# CONNECTORS2.net
KiCad netlist of a schematic drawn in Altium Designer
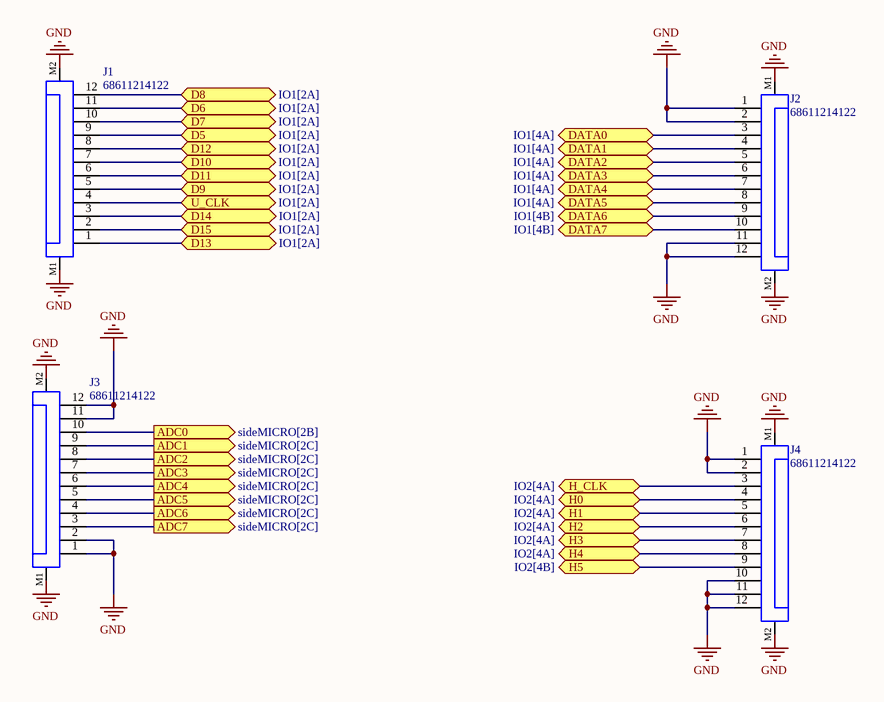
[diagram p0: CONNECTORS2.SchDoc]

(export (version "E")
  (design (tool "Eeschema 10.0.6"))
  (components
    (comp (ref "J1")
      (value "68611214122")
      (footprint "68611214122")
      (libsource (lib "Altium Content Vault") (part "FPC - 12P - 2MP"))
    )
    (comp (ref "J2")
      (value "68611214122")
      (footprint "68611214122")
      (libsource (lib "Altium Content Vault") (part "FPC - 12P - 2MP"))
    )
    (comp (ref "J3")
      (value "68611214122")
      (footprint "68611214122")
      (libsource (lib "Altium Content Vault") (part "FPC - 12P - 2MP"))
    )
    (comp (ref "J4")
      (value "68611214122")
      (footprint "68611214122")
      (libsource (lib "Altium Content Vault") (part "FPC - 12P - 2MP"))
    )
  )
  (nets
    (net (code "1") (name "/ADC0") (class "Default")
      (node (ref "J3") (pin "10") (pinfunction "10_10") (pintype "passive"))
    )
    (net (code "2") (name "/ADC1") (class "Default")
      (node (ref "J3") (pin "9") (pinfunction "9_9") (pintype "passive"))
    )
    (net (code "3") (name "/ADC2") (class "Default")
      (node (ref "J3") (pin "8") (pinfunction "8_8") (pintype "passive"))
    )
    (net (code "4") (name "/ADC3") (class "Default")
      (node (ref "J3") (pin "7") (pinfunction "7_7") (pintype "passive"))
    )
    (net (code "5") (name "/ADC4") (class "Default")
      (node (ref "J3") (pin "6") (pinfunction "6_6") (pintype "passive"))
    )
    (net (code "6") (name "/ADC5") (class "Default")
      (node (ref "J3") (pin "5") (pinfunction "5_5") (pintype "passive"))
    )
    (net (code "7") (name "/ADC6") (class "Default")
      (node (ref "J3") (pin "4") (pinfunction "4_4") (pintype "passive"))
    )
    (net (code "8") (name "/ADC7") (class "Default")
      (node (ref "J3") (pin "3") (pinfunction "3_3") (pintype "passive"))
    )
    (net (code "9") (name "/D5") (class "Default")
      (node (ref "J1") (pin "9") (pinfunction "9_9") (pintype "passive"))
    )
    (net (code "10") (name "/D6") (class "Default")
      (node (ref "J1") (pin "11") (pinfunction "11_11") (pintype "passive"))
    )
    (net (code "11") (name "/D7") (class "Default")
      (node (ref "J1") (pin "10") (pinfunction "10_10") (pintype "passive"))
    )
    (net (code "12") (name "/D8") (class "Default")
      (node (ref "J1") (pin "12") (pinfunction "12_12") (pintype "passive"))
    )
    (net (code "13") (name "/D9") (class "Default")
      (node (ref "J1") (pin "5") (pinfunction "5_5") (pintype "passive"))
    )
    (net (code "14") (name "/D10") (class "Default")
      (node (ref "J1") (pin "7") (pinfunction "7_7") (pintype "passive"))
    )
    (net (code "15") (name "/D11") (class "Default")
      (node (ref "J1") (pin "6") (pinfunction "6_6") (pintype "passive"))
    )
    (net (code "16") (name "/D12") (class "Default")
      (node (ref "J1") (pin "8") (pinfunction "8_8") (pintype "passive"))
    )
    (net (code "17") (name "/D13") (class "Default")
      (node (ref "J1") (pin "1") (pinfunction "1_1") (pintype "passive"))
    )
    (net (code "18") (name "/D14") (class "Default")
      (node (ref "J1") (pin "3") (pinfunction "3_3") (pintype "passive"))
    )
    (net (code "19") (name "/D15") (class "Default")
      (node (ref "J1") (pin "2") (pinfunction "2_2") (pintype "passive"))
    )
    (net (code "20") (name "/DATA0") (class "Default")
      (node (ref "J2") (pin "3") (pinfunction "3_3") (pintype "passive"))
    )
    (net (code "21") (name "/DATA1") (class "Default")
      (node (ref "J2") (pin "4") (pinfunction "4_4") (pintype "passive"))
    )
    (net (code "22") (name "/DATA2") (class "Default")
      (node (ref "J2") (pin "5") (pinfunction "5_5") (pintype "passive"))
    )
    (net (code "23") (name "/DATA3") (class "Default")
      (node (ref "J2") (pin "6") (pinfunction "6_6") (pintype "passive"))
    )
    (net (code "24") (name "/DATA4") (class "Default")
      (node (ref "J2") (pin "7") (pinfunction "7_7") (pintype "passive"))
    )
    (net (code "25") (name "/DATA5") (class "Default")
      (node (ref "J2") (pin "8") (pinfunction "8_8") (pintype "passive"))
    )
    (net (code "26") (name "/DATA6") (class "Default")
      (node (ref "J2") (pin "9") (pinfunction "9_9") (pintype "passive"))
    )
    (net (code "27") (name "/DATA7") (class "Default")
      (node (ref "J2") (pin "10") (pinfunction "10_10") (pintype "passive"))
    )
    (net (code "28") (name "/H0") (class "Default")
      (node (ref "J4") (pin "4") (pinfunction "4_4") (pintype "passive"))
    )
    (net (code "29") (name "/H1") (class "Default")
      (node (ref "J4") (pin "5") (pinfunction "5_5") (pintype "passive"))
    )
    (net (code "30") (name "/H2") (class "Default")
      (node (ref "J4") (pin "6") (pinfunction "6_6") (pintype "passive"))
    )
    (net (code "31") (name "/H3") (class "Default")
      (node (ref "J4") (pin "7") (pinfunction "7_7") (pintype "passive"))
    )
    (net (code "32") (name "/H4") (class "Default")
      (node (ref "J4") (pin "8") (pinfunction "8_8") (pintype "passive"))
    )
    (net (code "33") (name "/H5") (class "Default")
      (node (ref "J4") (pin "9") (pinfunction "9_9") (pintype "passive"))
    )
    (net (code "34") (name "/H_CLK") (class "Default")
      (node (ref "J4") (pin "3") (pinfunction "3_3") (pintype "passive"))
    )
    (net (code "35") (name "/U_CLK") (class "Default")
      (node (ref "J1") (pin "4") (pinfunction "4_4") (pintype "passive"))
    )
    (net (code "36") (name "GND") (class "Default")
      (node (ref "J1") (pin "M1") (pinfunction "M1_M1") (pintype "passive"))
      (node (ref "J1") (pin "M2") (pinfunction "M2_M2") (pintype "passive"))
      (node (ref "J2") (pin "1") (pinfunction "1_1") (pintype "passive"))
      (node (ref "J2") (pin "11") (pinfunction "11_11") (pintype "passive"))
      (node (ref "J2") (pin "12") (pinfunction "12_12") (pintype "passive"))
      (node (ref "J2") (pin "2") (pinfunction "2_2") (pintype "passive"))
      (node (ref "J2") (pin "M1") (pinfunction "M1_M1") (pintype "passive"))
      (node (ref "J2") (pin "M2") (pinfunction "M2_M2") (pintype "passive"))
      (node (ref "J3") (pin "1") (pinfunction "1_1") (pintype "passive"))
      (node (ref "J3") (pin "11") (pinfunction "11_11") (pintype "passive"))
      (node (ref "J3") (pin "12") (pinfunction "12_12") (pintype "passive"))
      (node (ref "J3") (pin "2") (pinfunction "2_2") (pintype "passive"))
      (node (ref "J3") (pin "M1") (pinfunction "M1_M1") (pintype "passive"))
      (node (ref "J3") (pin "M2") (pinfunction "M2_M2") (pintype "passive"))
      (node (ref "J4") (pin "1") (pinfunction "1_1") (pintype "passive"))
      (node (ref "J4") (pin "10") (pinfunction "10_10") (pintype "passive"))
      (node (ref "J4") (pin "11") (pinfunction "11_11") (pintype "passive"))
      (node (ref "J4") (pin "12") (pinfunction "12_12") (pintype "passive"))
      (node (ref "J4") (pin "2") (pinfunction "2_2") (pintype "passive"))
      (node (ref "J4") (pin "M1") (pinfunction "M1_M1") (pintype "passive"))
      (node (ref "J4") (pin "M2") (pinfunction "M2_M2") (pintype "passive"))
    )
  )
)
